# control.net
KiCad netlist of a schematic drawn in Altium Designer
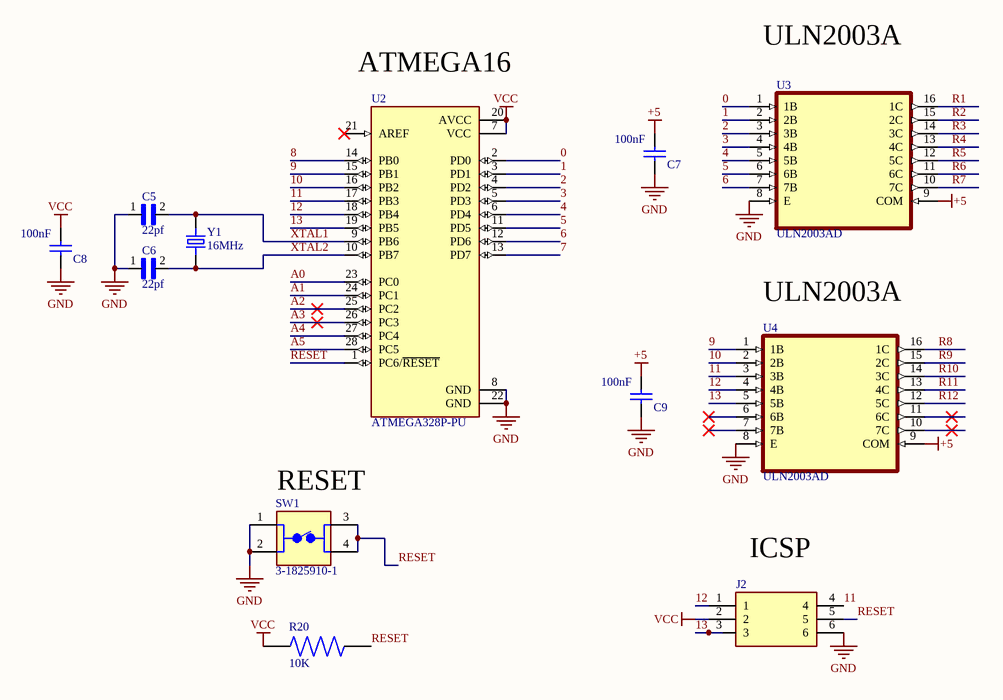
[diagram p0: control.SchDoc]

(export (version "E")
  (design (tool "Eeschema 10.0.6"))
  (components
    (comp (ref "C5")
      (value "22pf")
      (footprint "CAPC2012X130N:CAPC2012X130N")
      (description "Cap Cer 22pf 50v C0g/Np0 0805")
      (fields (field (name "MF") "Syfer") (field (name "MP") "0805Y0500220JCT"))
      (libsource (lib "control") (part "0805Y0500220JCT"))
    )
    (comp (ref "C6")
      (value "22pf")
      (footprint "CAPC2012X130N:CAPC2012X130N")
      (description "Cap Cer 22pf 50v C0g/Np0 0805")
      (fields (field (name "MF") "Syfer") (field (name "MP") "0805Y0500220JCT"))
      (libsource (lib "control") (part "0805Y0500220JCT"))
    )
    (comp (ref "C7")
      (value "100nF")
      (footprint "WCAP-CSGP_0805_L2W1.25H0.8_Reflow")
      (description "WCAP-CSGP Multilayer Ceramic Chip Capacitor, General Purpose, size 0805, X7R, 100nF, 25VDC")
      (fields
        (field (name "MANUFACTURER PART NUMBER") "885012207072")
        (field (name "MANUFACTURER") "Wurth Elektronik")
      )
      (libsource (lib "input") (part "885012207072"))
    )
    (comp (ref "C8")
      (value "100nF")
      (footprint "WCAP-CSGP_0805_L2W1.25H0.8_Reflow")
      (description "WCAP-CSGP Multilayer Ceramic Chip Capacitor, General Purpose, size 0805, X7R, 100nF, 25VDC")
      (fields
        (field (name "MANUFACTURER PART NUMBER") "885012207072")
        (field (name "MANUFACTURER") "Wurth Elektronik")
      )
      (libsource (lib "input") (part "885012207072"))
    )
    (comp (ref "C9")
      (value "100nF")
      (footprint "WCAP-CSGP_0805_L2W1.25H0.8_Reflow")
      (description "WCAP-CSGP Multilayer Ceramic Chip Capacitor, General Purpose, size 0805, X7R, 100nF, 25VDC")
      (fields
        (field (name "MANUFACTURER PART NUMBER") "885012207072")
        (field (name "MANUFACTURER") "Wurth Elektronik")
      )
      (libsource (lib "input") (part "885012207072"))
    )
    (comp (ref "J2")
      (value "5-146257-3")
      (footprint "TE_5-146257-3")
      (description "Header; Breakaway; 0.100 x 0.100 in.; PC Board; Dual; 6; 0.025 in.; 0.12 in.")
      (fields (field (name "MF") "TE Connectivity"))
      (libsource (lib "control") (part "5-146257-3"))
    )
    (comp (ref "R20")
      (value "10K")
      (footprint "RESC3216X70N")
      (description "Res 1206 10 Ohm 5% 1/8W Â±500ppm/Â°C Molded SMD SMD T/R")
      (fields (field (name "TOLERANCE") "5%") (field (name "MP") "FCR1206J10R"))
      (libsource (lib "input") (part "FCR1206J10R"))
    )
    (comp (ref "SW1")
      (value "3-1825910-1")
      (footprint "TE_3-1825910-1")
      (description "Switch Push Button OFF (ON) SPST Round Button 0.05A 24VDC Momentary Contact PC Pins Thru-Hole")
      (fields (field (name "MF") "TE Connectivity"))
      (libsource (lib "control") (part "3-1825910-1"))
    )
    (comp (ref "U2")
      (value "ATMEGA328P-PU")
      (footprint "control:DIL28")
      (description "ATmega Series 20 MHz 32 KB Flash 2 KB SRAM 8-Bit Microcontroller - DIP-28")
      (libsource (lib "control") (part "ATMEGA328P-PU"))
    )
    (comp (ref "U3")
      (value "ULN2003AD")
      (footprint "SOIC127P600X175-16N")
      (description "50-V, 7-ch darlington transistor array, -20C to 70C")
      (fields (field (name "MF") "Texas Instruments"))
      (libsource (lib "control") (part "ULN2003AD"))
    )
    (comp (ref "U4")
      (value "ULN2003AD")
      (footprint "SOIC127P600X175-16N")
      (description "50-V, 7-ch darlington transistor array, -20C to 70C")
      (fields (field (name "MF") "Texas Instruments"))
      (libsource (lib "control") (part "ULN2003AD"))
    )
    (comp (ref "Y1")
      (value "16MHz")
      (footprint "SnapEDApcb:XTAL_ECS-160-20-3X-TR")
      (description "16MHz Â±30ppm Crystal 20pF 50 Ohms HC-49/US")
      (fields (field (name "DIGI-KEY_PART_NUMBER") "XC1776CT-ND") (field (name "MP") "ECS-160-20-3X-TR"))
      (libsource (lib "control") (part "ECS-160-20-3X-TR"))
    )
  )
  (nets
    (net (code "1") (name "+5") (class "Default")
      (node (ref "C7") (pin "2") (pinfunction "2_2") (pintype "passive"))
      (node (ref "C9") (pin "2") (pinfunction "2_2") (pintype "passive"))
      (node (ref "U3") (pin "9") (pinfunction "COM_9") (pintype "input"))
      (node (ref "U4") (pin "9") (pinfunction "COM_9") (pintype "input"))
    )
    (net (code "2") (name "/0") (class "Default")
      (node (ref "U2") (pin "2") (pinfunction "PD0_2") (pintype "bidirectional"))
      (node (ref "U3") (pin "1") (pinfunction "1B_1") (pintype "input"))
    )
    (net (code "3") (name "/1") (class "Default")
      (node (ref "U2") (pin "3") (pinfunction "PD1_3") (pintype "bidirectional"))
      (node (ref "U3") (pin "2") (pinfunction "2B_2") (pintype "input"))
    )
    (net (code "4") (name "/2") (class "Default")
      (node (ref "U2") (pin "4") (pinfunction "PD2_4") (pintype "bidirectional"))
      (node (ref "U3") (pin "3") (pinfunction "3B_3") (pintype "input"))
    )
    (net (code "5") (name "/3") (class "Default")
      (node (ref "U2") (pin "5") (pinfunction "PD3_5") (pintype "bidirectional"))
      (node (ref "U3") (pin "4") (pinfunction "4B_4") (pintype "input"))
    )
    (net (code "6") (name "/4") (class "Default")
      (node (ref "U2") (pin "6") (pinfunction "PD4_6") (pintype "bidirectional"))
      (node (ref "U3") (pin "5") (pinfunction "5B_5") (pintype "input"))
    )
    (net (code "7") (name "/5") (class "Default")
      (node (ref "U2") (pin "11") (pinfunction "PD5_11") (pintype "bidirectional"))
      (node (ref "U3") (pin "6") (pinfunction "6B_6") (pintype "input"))
    )
    (net (code "8") (name "/6") (class "Default")
      (node (ref "U2") (pin "12") (pinfunction "PD6_12") (pintype "bidirectional"))
      (node (ref "U3") (pin "7") (pinfunction "7B_7") (pintype "input"))
    )
    (net (code "9") (name "/7") (class "Default")
      (node (ref "U2") (pin "13") (pinfunction "PD7_13") (pintype "bidirectional"))
    )
    (net (code "10") (name "/8") (class "Default")
      (node (ref "U2") (pin "14") (pinfunction "PB0_14") (pintype "bidirectional"))
    )
    (net (code "11") (name "/9") (class "Default")
      (node (ref "U2") (pin "15") (pinfunction "PB1_15") (pintype "bidirectional"))
      (node (ref "U4") (pin "1") (pinfunction "1B_1") (pintype "input"))
    )
    (net (code "12") (name "/10") (class "Default")
      (node (ref "U2") (pin "16") (pinfunction "PB2_16") (pintype "bidirectional"))
      (node (ref "U4") (pin "2") (pinfunction "2B_2") (pintype "input"))
    )
    (net (code "13") (name "/11") (class "Default")
      (node (ref "J2") (pin "4") (pinfunction "4_4") (pintype "passive"))
      (node (ref "U2") (pin "17") (pinfunction "PB3_17") (pintype "bidirectional"))
      (node (ref "U4") (pin "3") (pinfunction "3B_3") (pintype "input"))
    )
    (net (code "14") (name "/12") (class "Default")
      (node (ref "J2") (pin "1") (pinfunction "1_1") (pintype "passive"))
      (node (ref "U2") (pin "18") (pinfunction "PB4_18") (pintype "bidirectional"))
      (node (ref "U4") (pin "4") (pinfunction "4B_4") (pintype "input"))
    )
    (net (code "15") (name "/13") (class "Default")
      (node (ref "J2") (pin "3") (pinfunction "3_3") (pintype "passive"))
      (node (ref "U2") (pin "19") (pinfunction "PB5_19") (pintype "bidirectional"))
      (node (ref "U4") (pin "5") (pinfunction "5B_5") (pintype "input"))
    )
    (net (code "16") (name "/A0") (class "Default")
      (node (ref "U2") (pin "23") (pinfunction "PC0_23") (pintype "bidirectional"))
    )
    (net (code "17") (name "/A1") (class "Default")
      (node (ref "U2") (pin "24") (pinfunction "PC1_24") (pintype "bidirectional"))
    )
    (net (code "18") (name "/A2") (class "Default")
      (node (ref "U2") (pin "25") (pinfunction "PC2_25") (pintype "bidirectional"))
    )
    (net (code "19") (name "/A3") (class "Default")
      (node (ref "U2") (pin "26") (pinfunction "PC3_26") (pintype "bidirectional"))
    )
    (net (code "20") (name "/A4") (class "Default")
      (node (ref "U2") (pin "27") (pinfunction "PC4_27") (pintype "bidirectional"))
    )
    (net (code "21") (name "/A5") (class "Default")
      (node (ref "U2") (pin "28") (pinfunction "PC5_28") (pintype "bidirectional"))
    )
    (net (code "22") (name "/R1") (class "Default")
      (node (ref "U3") (pin "16") (pinfunction "1C_16") (pintype "output"))
    )
    (net (code "23") (name "/R2") (class "Default")
      (node (ref "U3") (pin "15") (pinfunction "2C_15") (pintype "output"))
    )
    (net (code "24") (name "/R3") (class "Default")
      (node (ref "U3") (pin "14") (pinfunction "3C_14") (pintype "output"))
    )
    (net (code "25") (name "/R4") (class "Default")
      (node (ref "U3") (pin "13") (pinfunction "4C_13") (pintype "output"))
    )
    (net (code "26") (name "/R5") (class "Default")
      (node (ref "U3") (pin "12") (pinfunction "5C_12") (pintype "output"))
    )
    (net (code "27") (name "/R6") (class "Default")
      (node (ref "U3") (pin "11") (pinfunction "6C_11") (pintype "output"))
    )
    (net (code "28") (name "/R7") (class "Default")
      (node (ref "U3") (pin "10") (pinfunction "7C_10") (pintype "output"))
    )
    (net (code "29") (name "/R8") (class "Default")
      (node (ref "U4") (pin "16") (pinfunction "1C_16") (pintype "output"))
    )
    (net (code "30") (name "/R9") (class "Default")
      (node (ref "U4") (pin "15") (pinfunction "2C_15") (pintype "output"))
    )
    (net (code "31") (name "/R10") (class "Default")
      (node (ref "U4") (pin "14") (pinfunction "3C_14") (pintype "output"))
    )
    (net (code "32") (name "/R11") (class "Default")
      (node (ref "U4") (pin "13") (pinfunction "4C_13") (pintype "output"))
    )
    (net (code "33") (name "/R12") (class "Default")
      (node (ref "U4") (pin "12") (pinfunction "5C_12") (pintype "output"))
    )
    (net (code "34") (name "/RESET") (class "Default")
      (node (ref "J2") (pin "5") (pinfunction "5_5") (pintype "passive"))
      (node (ref "R20") (pin "2") (pinfunction "2_2") (pintype "passive"))
      (node (ref "SW1") (pin "3") (pinfunction "3_3") (pintype "passive"))
      (node (ref "SW1") (pin "4") (pinfunction "4_4") (pintype "passive"))
      (node (ref "U2") (pin "1") (pinfunction "PC6/~{RESET}_1") (pintype "bidirectional"))
    )
    (net (code "35") (name "/XTAL1") (class "Default")
      (node (ref "C5") (pin "2") (pinfunction "2_2") (pintype "passive"))
      (node (ref "U2") (pin "9") (pinfunction "PB6_9") (pintype "bidirectional"))
      (node (ref "Y1") (pin "2") (pinfunction "2_2") (pintype "passive"))
    )
    (net (code "36") (name "/XTAL2") (class "Default")
      (node (ref "C6") (pin "2") (pinfunction "2_2") (pintype "passive"))
      (node (ref "U2") (pin "10") (pinfunction "PB7_10") (pintype "bidirectional"))
      (node (ref "Y1") (pin "1") (pinfunction "1_1") (pintype "passive"))
    )
    (net (code "37") (name "GND") (class "Default")
      (node (ref "C5") (pin "1") (pinfunction "1_1") (pintype "passive"))
      (node (ref "C6") (pin "1") (pinfunction "1_1") (pintype "passive"))
      (node (ref "C7") (pin "1") (pinfunction "1_1") (pintype "passive"))
      (node (ref "C8") (pin "1") (pinfunction "1_1") (pintype "passive"))
      (node (ref "C9") (pin "1") (pinfunction "1_1") (pintype "passive"))
      (node (ref "J2") (pin "6") (pinfunction "6_6") (pintype "passive"))
      (node (ref "SW1") (pin "1") (pinfunction "1_1") (pintype "passive"))
      (node (ref "SW1") (pin "2") (pinfunction "2_2") (pintype "passive"))
      (node (ref "U2") (pin "22") (pinfunction "GND_22") (pintype "power_in"))
      (node (ref "U2") (pin "8") (pinfunction "GND_8") (pintype "power_in"))
      (node (ref "U3") (pin "8") (pinfunction "E_8") (pintype "input"))
      (node (ref "U4") (pin "8") (pinfunction "E_8") (pintype "input"))
    )
    (net (code "38") (name "VCC") (class "Default")
      (node (ref "C8") (pin "2") (pinfunction "2_2") (pintype "passive"))
      (node (ref "J2") (pin "2") (pinfunction "2_2") (pintype "passive"))
      (node (ref "R20") (pin "1") (pinfunction "1_1") (pintype "passive"))
      (node (ref "U2") (pin "20") (pinfunction "AVCC_20") (pintype "power_in"))
      (node (ref "U2") (pin "7") (pinfunction "VCC_7") (pintype "power_in"))
    )
    (net (code "39") (name "unconnected-(U2-AREF-Pad21)") (class "Default")
      (node (ref "U2") (pin "21") (pinfunction "AREF_21") (pintype "input+no_connect"))
    )
    (net (code "40") (name "unconnected-(U4-6B-Pad6)") (class "Default")
      (node (ref "U4") (pin "6") (pinfunction "6B_6") (pintype "input+no_connect"))
    )
    (net (code "41") (name "unconnected-(U4-6C-Pad11)") (class "Default")
      (node (ref "U4") (pin "11") (pinfunction "6C_11") (pintype "output"))
    )
    (net (code "42") (name "unconnected-(U4-7B-Pad7)") (class "Default")
      (node (ref "U4") (pin "7") (pinfunction "7B_7") (pintype "input+no_connect"))
    )
    (net (code "43") (name "unconnected-(U4-7C-Pad10)") (class "Default")
      (node (ref "U4") (pin "10") (pinfunction "7C_10") (pintype "output"))
    )
  )
)
